# ventmon_t0_5c.net
KiCad netlist of a schematic drawn in EAGLE
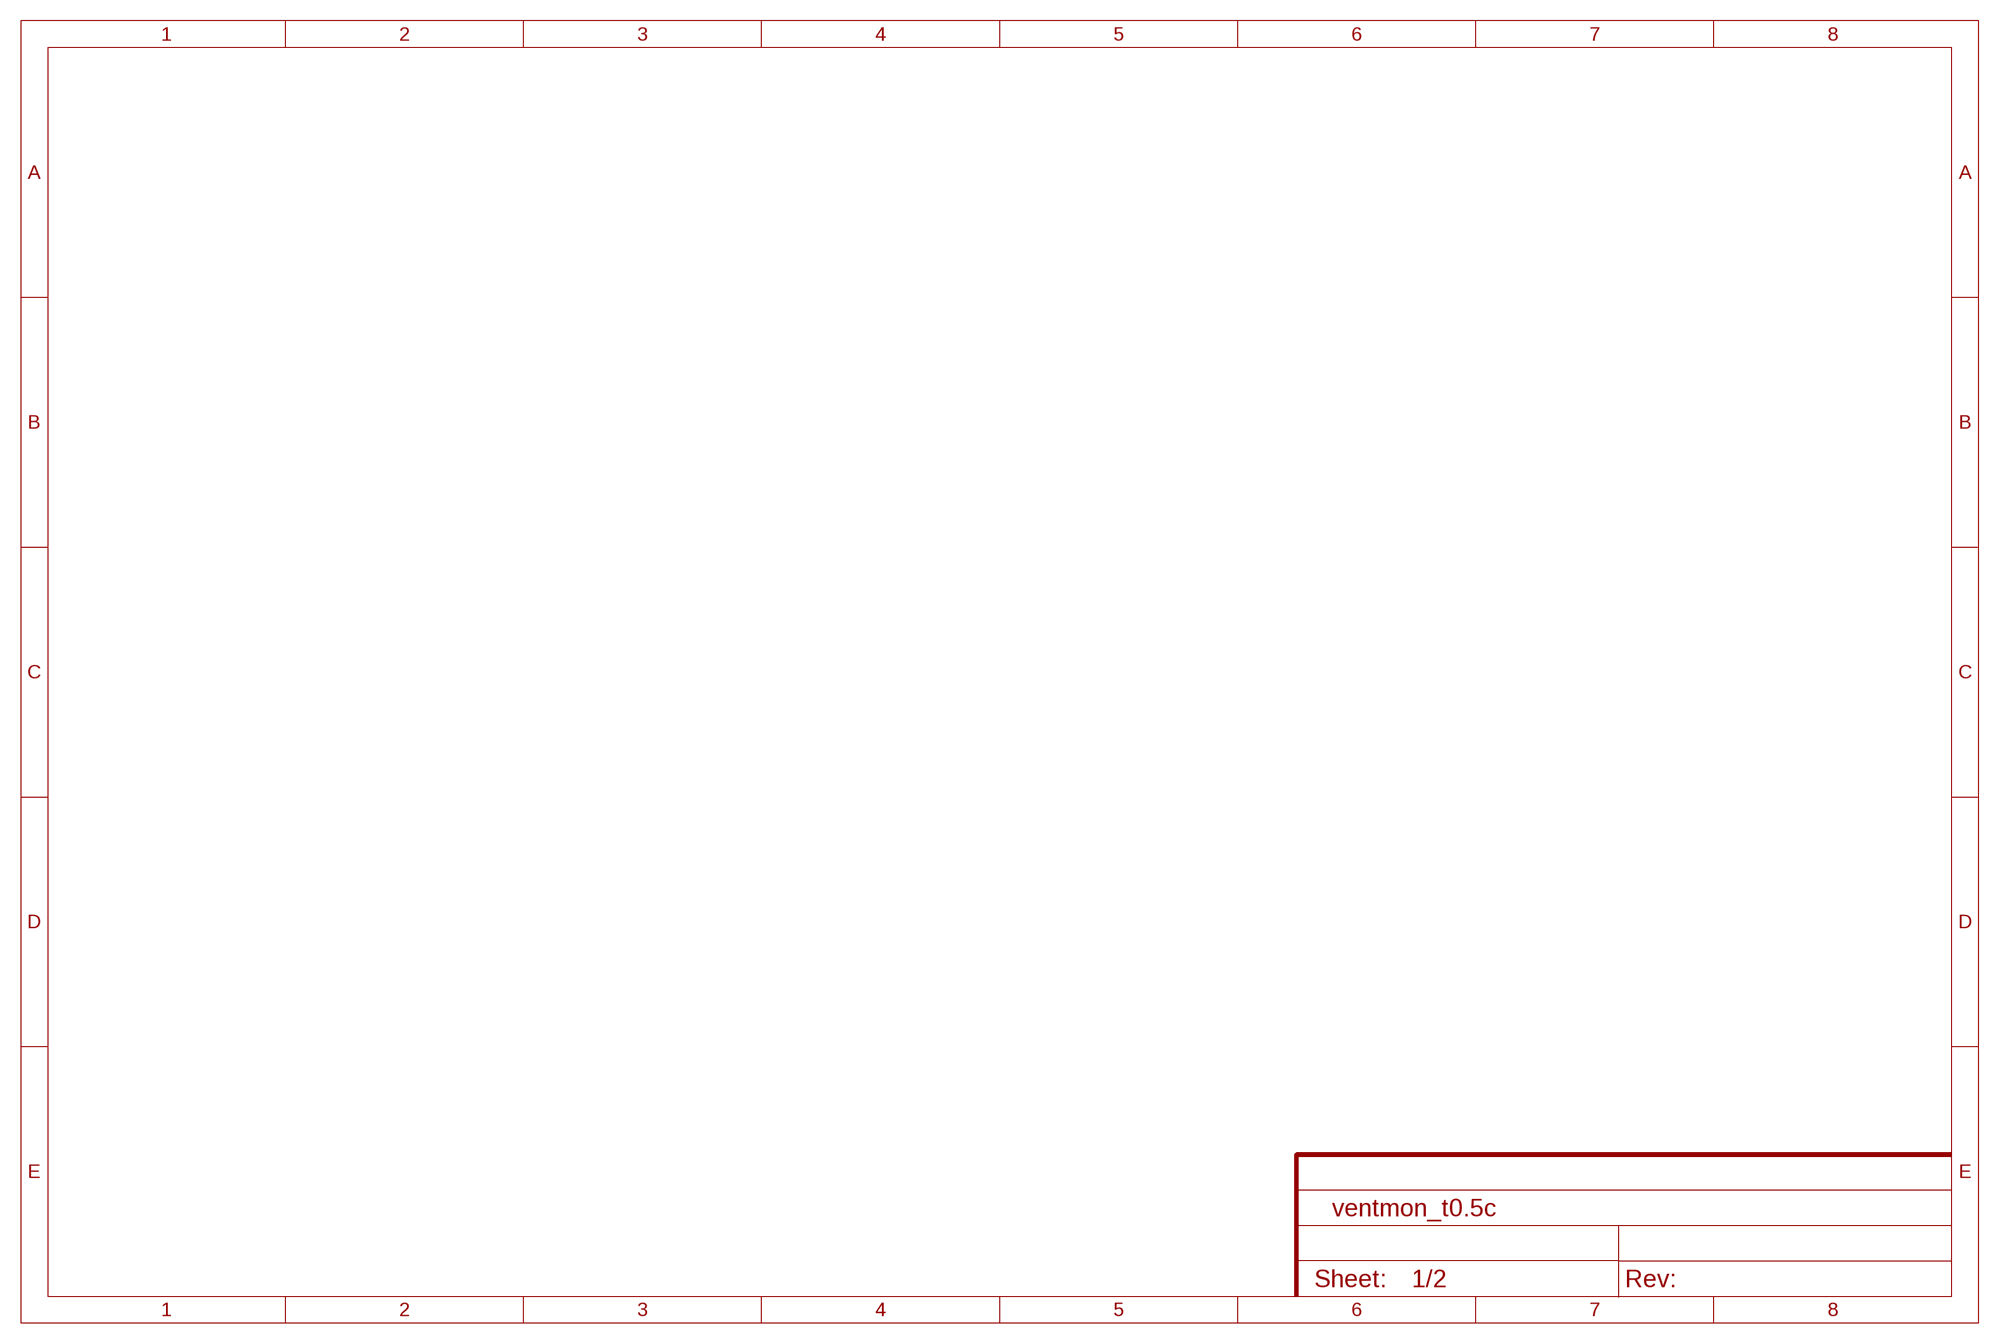
[diagram p0: schematic, sheet 1]
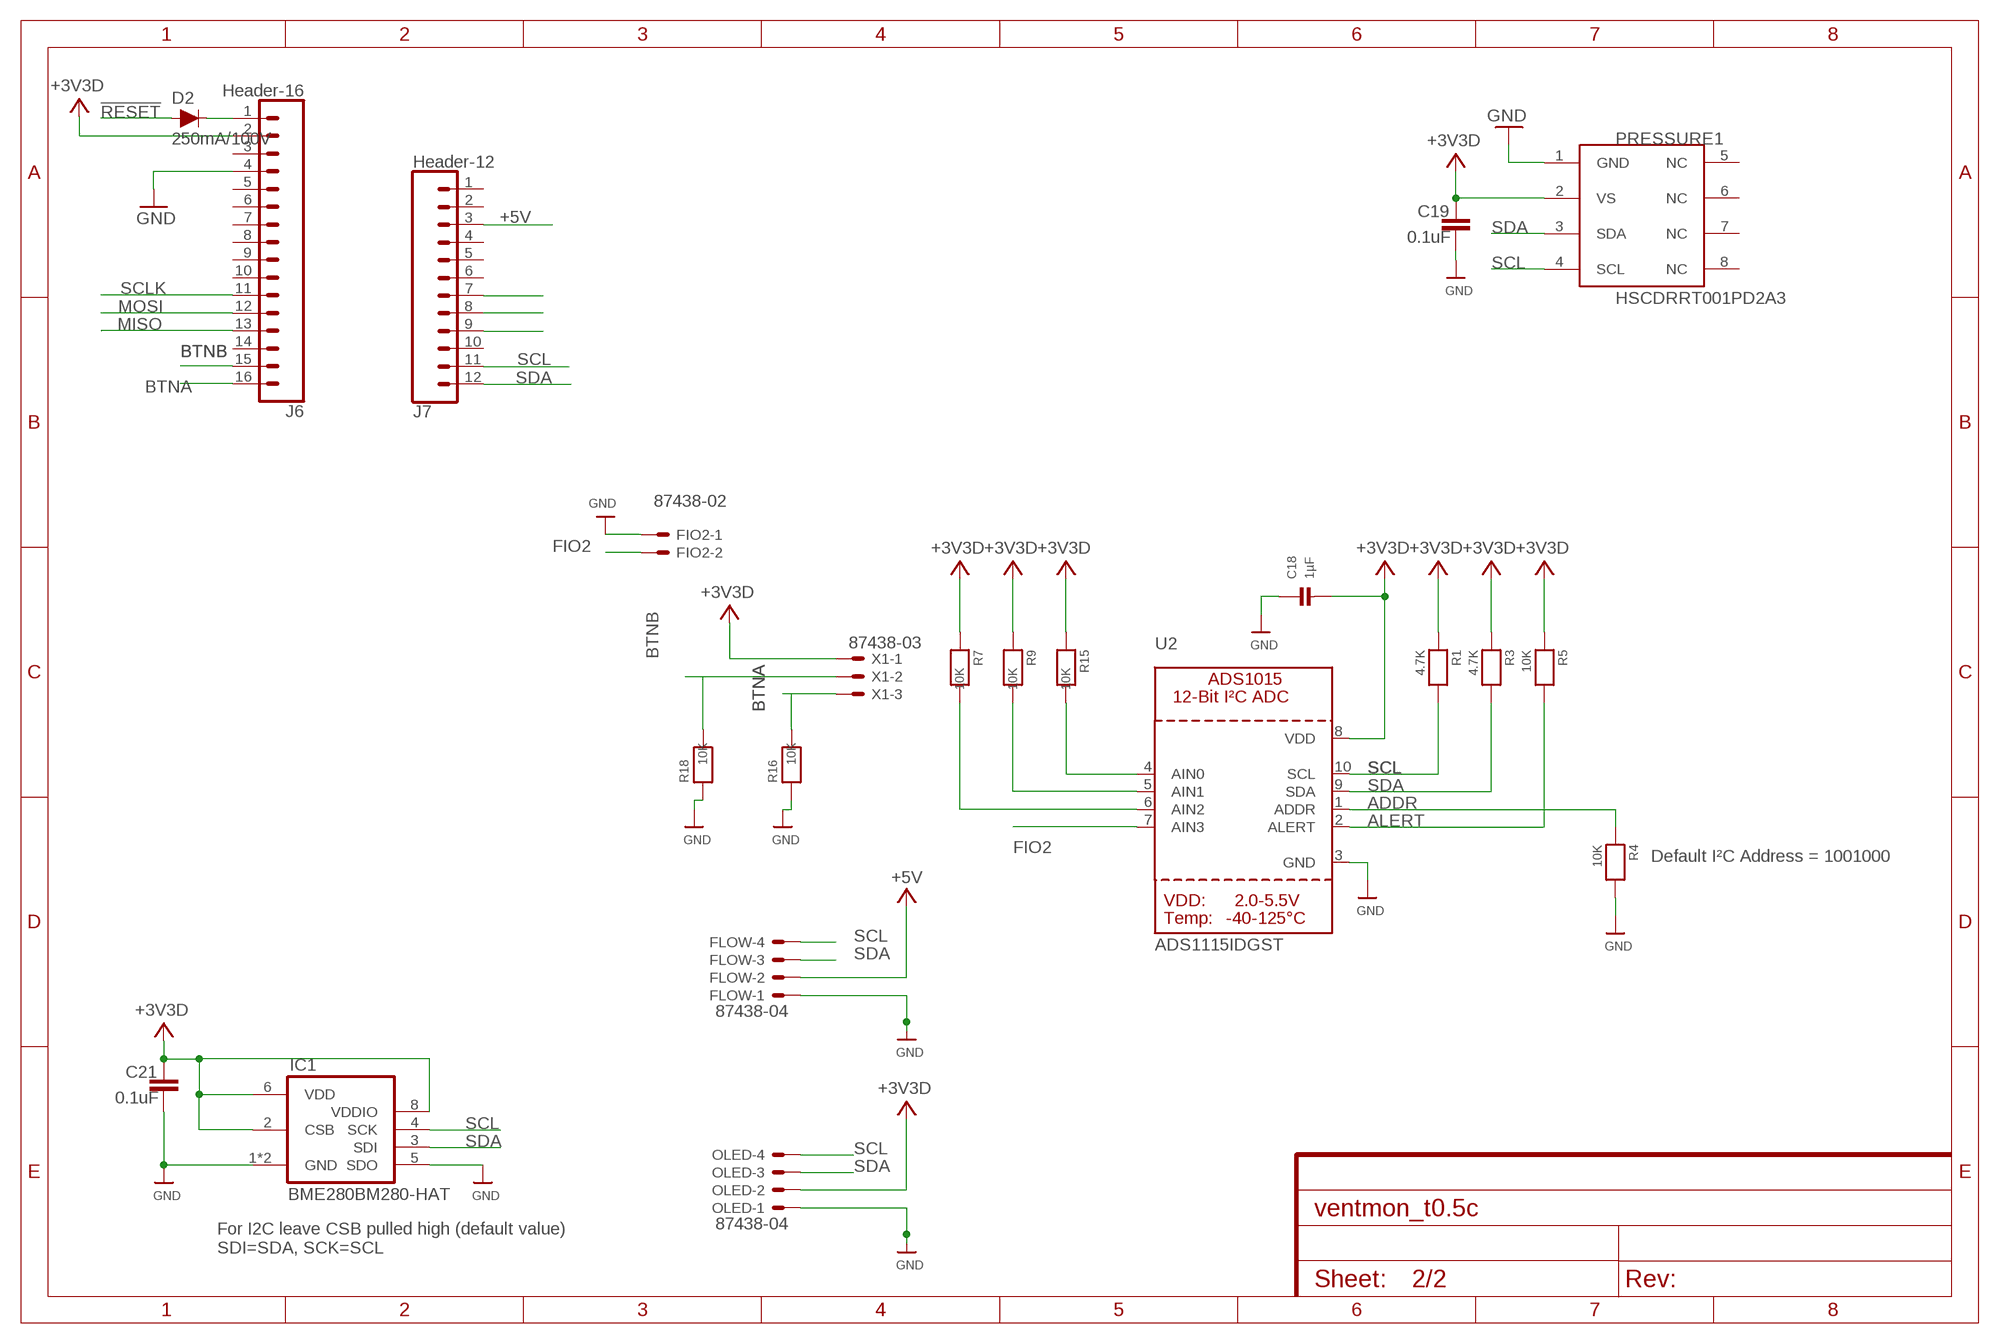
[diagram p1: schematic, sheet 2]

(export (version "E")
  (design (tool "Eeschema 10.0.6"))
  (components
    (comp (ref "C18")
      (value "1µF")
      (footprint "eagle-import:0603")
      (libsource (lib "eagle-import") (part "CAP_CERAMIC0603"))
    )
    (comp (ref "C19")
      (value "0.1uF")
      (footprint "eagle-import:C0402_B")
      (libsource (lib "eagle-import") (part "CAP_1"))
    )
    (comp (ref "C21")
      (value "0.1uF")
      (footprint "eagle-import:C0402_B")
      (libsource (lib "eagle-import") (part "CAP_1"))
    )
    (comp (ref "D2")
      (value "250mA/100V")
      (footprint "eagle-import:SOD-323")
      (libsource (lib "eagle-import") (part "DIODE-BAS16J"))
    )
    (comp (ref "FIO2")
      (value "87438-02")
      (footprint "eagle-import:87438-02")
      (fields (field (name "MF") "MOLEX"))
      (libsource (lib "eagle-import") (part "87438-02"))
    )
    (comp (ref "FLOW")
      (value "87438-04")
      (footprint "eagle-import:87438-04")
      (fields (field (name "MF") "MOLEX"))
      (libsource (lib "eagle-import") (part "87438-04"))
    )
    (comp (ref "IC1")
      (value "BME280BM280-HAT")
      (footprint "eagle-import:BME280-HAT")
      (libsource (lib "eagle-import") (part "BME280BM280-HAT"))
    )
    (comp (ref "J6")
      (value "Header-16")
      (footprint "eagle-import:1X16")
      (libsource (lib "eagle-import") (part "CONN_16"))
    )
    (comp (ref "J7")
      (value "Header-12")
      (footprint "eagle-import:1X12")
      (libsource (lib "eagle-import") (part "CONN_12"))
    )
    (comp (ref "OLED")
      (value "87438-04")
      (footprint "eagle-import:87438-04")
      (fields (field (name "MF") "MOLEX"))
      (libsource (lib "eagle-import") (part "87438-04"))
    )
    (comp (ref "PRESSURE1")
      (value "HSCDRRT001PD2A3")
      (footprint "eagle-import:DIP1330W46P254L1000H616Q8B")
      (libsource (lib "eagle-import") (part "HSCDRRT001PD2A3"))
    )
    (comp (ref "R1")
      (value "4.7K")
      (footprint "eagle-import:0603")
      (libsource (lib "eagle-import") (part "RESISTOR0603"))
    )
    (comp (ref "R3")
      (value "4.7K")
      (footprint "eagle-import:0603")
      (libsource (lib "eagle-import") (part "RESISTOR0603"))
    )
    (comp (ref "R4")
      (value "10K")
      (footprint "eagle-import:0603")
      (libsource (lib "eagle-import") (part "RESISTOR0603"))
    )
    (comp (ref "R5")
      (value "10K")
      (footprint "eagle-import:0603")
      (libsource (lib "eagle-import") (part "RESISTOR0603"))
    )
    (comp (ref "R7")
      (value "10K")
      (footprint "eagle-import:0603")
      (libsource (lib "eagle-import") (part "RESISTOR0603"))
    )
    (comp (ref "R9")
      (value "10K")
      (footprint "eagle-import:0603")
      (libsource (lib "eagle-import") (part "RESISTOR0603"))
    )
    (comp (ref "R15")
      (value "10K")
      (footprint "eagle-import:0603")
      (libsource (lib "eagle-import") (part "RESISTOR0603"))
    )
    (comp (ref "R16")
      (value "10K")
      (footprint "eagle-import:0603")
      (libsource (lib "eagle-import") (part "RESISTOR0603"))
    )
    (comp (ref "R18")
      (value "10K")
      (footprint "eagle-import:0603")
      (libsource (lib "eagle-import") (part "RESISTOR0603"))
    )
    (comp (ref "U2")
      (value "ADS1115IDGST")
      (footprint "eagle-import:MSOP10")
      (libsource (lib "eagle-import") (part "ADC_ADS1015"))
    )
    (comp (ref "X1")
      (value "87438-03")
      (footprint "eagle-import:87438-03")
      (fields (field (name "MF") "MOLEX"))
      (libsource (lib "eagle-import") (part "87438-03"))
    )
  )
  (nets
    (net (code "1") (name "+3V3") (class "Default")
      (node (ref "C18") (pin "2") (pinfunction "P$2_2") (pintype "passive"))
      (node (ref "C19") (pin "2") (pinfunction "P$2_2") (pintype "passive"))
      (node (ref "C21") (pin "2") (pinfunction "P$2_2") (pintype "passive"))
      (node (ref "IC1") (pin "2") (pinfunction "CSB_2") (pintype "input"))
      (node (ref "IC1") (pin "6") (pinfunction "VDD_6") (pintype "power_in"))
      (node (ref "IC1") (pin "8") (pinfunction "VDDIO_8") (pintype "power_in"))
      (node (ref "J6") (pin "2") (pinfunction "2_2") (pintype "passive"))
      (node (ref "OLED") (pin "2") (pinfunction "S_2") (pintype "passive"))
      (node (ref "PRESSURE1") (pin "2") (pinfunction "VS_2") (pintype "bidirectional"))
      (node (ref "R1") (pin "1") (pinfunction "1_1") (pintype "passive"))
      (node (ref "R15") (pin "1") (pinfunction "1_1") (pintype "passive"))
      (node (ref "R3") (pin "1") (pinfunction "1_1") (pintype "passive"))
      (node (ref "R5") (pin "1") (pinfunction "1_1") (pintype "passive"))
      (node (ref "R7") (pin "1") (pinfunction "1_1") (pintype "passive"))
      (node (ref "R9") (pin "1") (pinfunction "1_1") (pintype "passive"))
      (node (ref "U2") (pin "8") (pinfunction "VDD_8") (pintype "bidirectional"))
      (node (ref "X1") (pin "1") (pinfunction "S_1") (pintype "passive"))
    )
    (net (code "2") (name "+5V") (class "Default")
      (node (ref "FLOW") (pin "2") (pinfunction "S_2") (pintype "passive"))
      (node (ref "J7") (pin "3") (pinfunction "3_3") (pintype "passive"))
    )
    (net (code "3") (name "ADDR") (class "Default")
      (node (ref "R4") (pin "1") (pinfunction "1_1") (pintype "passive"))
      (node (ref "U2") (pin "1") (pinfunction "ADDR_1") (pintype "bidirectional"))
    )
    (net (code "4") (name "ALERT") (class "Default")
      (node (ref "R5") (pin "2") (pinfunction "2_2") (pintype "passive"))
      (node (ref "U2") (pin "2") (pinfunction "ALERT_2") (pintype "bidirectional"))
    )
    (net (code "5") (name "BTNA") (class "Default")
      (node (ref "J6") (pin "16") (pinfunction "16_16") (pintype "passive"))
      (node (ref "R16") (pin "2") (pinfunction "2_2") (pintype "passive"))
      (node (ref "X1") (pin "3") (pinfunction "S_3") (pintype "passive"))
    )
    (net (code "6") (name "BTNB") (class "Default")
      (node (ref "J6") (pin "15") (pinfunction "15_15") (pintype "passive"))
      (node (ref "R18") (pin "2") (pinfunction "2_2") (pintype "passive"))
      (node (ref "X1") (pin "2") (pinfunction "S_2") (pintype "passive"))
    )
    (net (code "7") (name "FIO2") (class "Default")
      (node (ref "FIO2") (pin "2") (pinfunction "S_2") (pintype "passive"))
      (node (ref "U2") (pin "7") (pinfunction "AIN3_7") (pintype "bidirectional"))
    )
    (net (code "8") (name "GND") (class "Default")
      (node (ref "C18") (pin "1") (pinfunction "P$1_1") (pintype "passive"))
      (node (ref "C19") (pin "1") (pinfunction "P$1_1") (pintype "passive"))
      (node (ref "C21") (pin "1") (pinfunction "P$1_1") (pintype "passive"))
      (node (ref "FIO2") (pin "1") (pinfunction "S_1") (pintype "passive"))
      (node (ref "FLOW") (pin "1") (pinfunction "S_1") (pintype "passive"))
      (node (ref "IC1") (pin "1") (pinfunction "GND_1") (pintype "power_in"))
      (node (ref "IC1") (pin "5") (pinfunction "SDO_5") (pintype "input"))
      (node (ref "IC1") (pin "7") (pinfunction "GND_7") (pintype "power_in"))
      (node (ref "J6") (pin "4") (pinfunction "4_4") (pintype "passive"))
      (node (ref "OLED") (pin "1") (pinfunction "S_1") (pintype "passive"))
      (node (ref "PRESSURE1") (pin "1") (pinfunction "GND_1") (pintype "bidirectional"))
      (node (ref "R16") (pin "1") (pinfunction "1_1") (pintype "passive"))
      (node (ref "R18") (pin "1") (pinfunction "1_1") (pintype "passive"))
      (node (ref "R4") (pin "2") (pinfunction "2_2") (pintype "passive"))
      (node (ref "U2") (pin "3") (pinfunction "GND_3") (pintype "bidirectional"))
    )
    (net (code "9") (name "MISO") (class "Default")
      (node (ref "J6") (pin "13") (pinfunction "13_13") (pintype "passive"))
    )
    (net (code "10") (name "MOSI") (class "Default")
      (node (ref "J6") (pin "12") (pinfunction "12_12") (pintype "passive"))
    )
    (net (code "11") (name "Net-(D2-PadC)") (class "Default")
      (node (ref "D2") (pin "C") (pinfunction "C_C") (pintype "passive"))
      (node (ref "J6") (pin "1") (pinfunction "1_1") (pintype "passive"))
    )
    (net (code "12") (name "Net-(U2-AIN0)") (class "Default")
      (node (ref "R15") (pin "2") (pinfunction "2_2") (pintype "passive"))
      (node (ref "U2") (pin "4") (pinfunction "AIN0_4") (pintype "bidirectional"))
    )
    (net (code "13") (name "Net-(U2-AIN1)") (class "Default")
      (node (ref "R9") (pin "2") (pinfunction "2_2") (pintype "passive"))
      (node (ref "U2") (pin "5") (pinfunction "AIN1_5") (pintype "bidirectional"))
    )
    (net (code "14") (name "Net-(U2-AIN2)") (class "Default")
      (node (ref "R7") (pin "2") (pinfunction "2_2") (pintype "passive"))
      (node (ref "U2") (pin "6") (pinfunction "AIN2_6") (pintype "bidirectional"))
    )
    (net (code "15") (name "SCL") (class "Default")
      (node (ref "FLOW") (pin "4") (pinfunction "S_4") (pintype "passive"))
      (node (ref "IC1") (pin "4") (pinfunction "SCK_4") (pintype "bidirectional"))
      (node (ref "J7") (pin "11") (pinfunction "11_11") (pintype "passive"))
      (node (ref "OLED") (pin "4") (pinfunction "S_4") (pintype "passive"))
      (node (ref "PRESSURE1") (pin "4") (pinfunction "SCL_4") (pintype "bidirectional"))
      (node (ref "R1") (pin "2") (pinfunction "2_2") (pintype "passive"))
      (node (ref "U2") (pin "10") (pinfunction "SCL_10") (pintype "bidirectional"))
    )
    (net (code "16") (name "SCLK") (class "Default")
      (node (ref "J6") (pin "11") (pinfunction "11_11") (pintype "passive"))
    )
    (net (code "17") (name "SDA") (class "Default")
      (node (ref "FLOW") (pin "3") (pinfunction "S_3") (pintype "passive"))
      (node (ref "IC1") (pin "3") (pinfunction "SDI_3") (pintype "bidirectional"))
      (node (ref "J7") (pin "12") (pinfunction "12_12") (pintype "passive"))
      (node (ref "OLED") (pin "3") (pinfunction "S_3") (pintype "passive"))
      (node (ref "PRESSURE1") (pin "3") (pinfunction "SDA_3") (pintype "bidirectional"))
      (node (ref "R3") (pin "2") (pinfunction "2_2") (pintype "passive"))
      (node (ref "U2") (pin "9") (pinfunction "SDA_9") (pintype "bidirectional"))
    )
    (net (code "18") (name "unconnected-(J6-Pad3)") (class "Default")
      (node (ref "J6") (pin "3") (pinfunction "3_3") (pintype "passive"))
    )
    (net (code "19") (name "unconnected-(J6-Pad5)") (class "Default")
      (node (ref "J6") (pin "5") (pinfunction "5_5") (pintype "passive"))
    )
    (net (code "20") (name "unconnected-(J6-Pad6)") (class "Default")
      (node (ref "J6") (pin "6") (pinfunction "6_6") (pintype "passive"))
    )
    (net (code "21") (name "unconnected-(J6-Pad7)") (class "Default")
      (node (ref "J6") (pin "7") (pinfunction "7_7") (pintype "passive"))
    )
    (net (code "22") (name "unconnected-(J6-Pad8)") (class "Default")
      (node (ref "J6") (pin "8") (pinfunction "8_8") (pintype "passive"))
    )
    (net (code "23") (name "unconnected-(J6-Pad9)") (class "Default")
      (node (ref "J6") (pin "9") (pinfunction "9_9") (pintype "passive"))
    )
    (net (code "24") (name "unconnected-(J6-Pad10)") (class "Default")
      (node (ref "J6") (pin "10") (pinfunction "10_10") (pintype "passive"))
    )
    (net (code "25") (name "unconnected-(J6-Pad14)") (class "Default")
      (node (ref "J6") (pin "14") (pinfunction "14_14") (pintype "passive"))
    )
    (net (code "26") (name "unconnected-(J7-Pad1)") (class "Default")
      (node (ref "J7") (pin "1") (pinfunction "1_1") (pintype "passive"))
    )
    (net (code "27") (name "unconnected-(J7-Pad2)") (class "Default")
      (node (ref "J7") (pin "2") (pinfunction "2_2") (pintype "passive"))
    )
    (net (code "28") (name "unconnected-(J7-Pad4)") (class "Default")
      (node (ref "J7") (pin "4") (pinfunction "4_4") (pintype "passive"))
    )
    (net (code "29") (name "unconnected-(J7-Pad5)") (class "Default")
      (node (ref "J7") (pin "5") (pinfunction "5_5") (pintype "passive"))
    )
    (net (code "30") (name "unconnected-(J7-Pad6)") (class "Default")
      (node (ref "J7") (pin "6") (pinfunction "6_6") (pintype "passive"))
    )
    (net (code "31") (name "unconnected-(J7-Pad7)") (class "Default")
      (node (ref "J7") (pin "7") (pinfunction "7_7") (pintype "passive"))
    )
    (net (code "32") (name "unconnected-(J7-Pad8)") (class "Default")
      (node (ref "J7") (pin "8") (pinfunction "8_8") (pintype "passive"))
    )
    (net (code "33") (name "unconnected-(J7-Pad9)") (class "Default")
      (node (ref "J7") (pin "9") (pinfunction "9_9") (pintype "passive"))
    )
    (net (code "34") (name "unconnected-(J7-Pad10)") (class "Default")
      (node (ref "J7") (pin "10") (pinfunction "10_10") (pintype "passive"))
    )
    (net (code "35") (name "unconnected-(PRESSURE1-NC-Pad5)") (class "Default")
      (node (ref "PRESSURE1") (pin "5") (pinfunction "NC_5") (pintype "bidirectional"))
    )
    (net (code "36") (name "unconnected-(PRESSURE1-NC-Pad6)") (class "Default")
      (node (ref "PRESSURE1") (pin "6") (pinfunction "NC_6") (pintype "bidirectional"))
    )
    (net (code "37") (name "unconnected-(PRESSURE1-NC-Pad7)") (class "Default")
      (node (ref "PRESSURE1") (pin "7") (pinfunction "NC_7") (pintype "bidirectional"))
    )
    (net (code "38") (name "unconnected-(PRESSURE1-NC-Pad8)") (class "Default")
      (node (ref "PRESSURE1") (pin "8") (pinfunction "NC_8") (pintype "bidirectional"))
    )
    (net (code "39") (name "~{RESET}") (class "Default")
      (node (ref "D2") (pin "A") (pinfunction "A_A") (pintype "passive"))
    )
  )
)
